# Master.net
KiCad netlist of a schematic drawn in Altium Designer
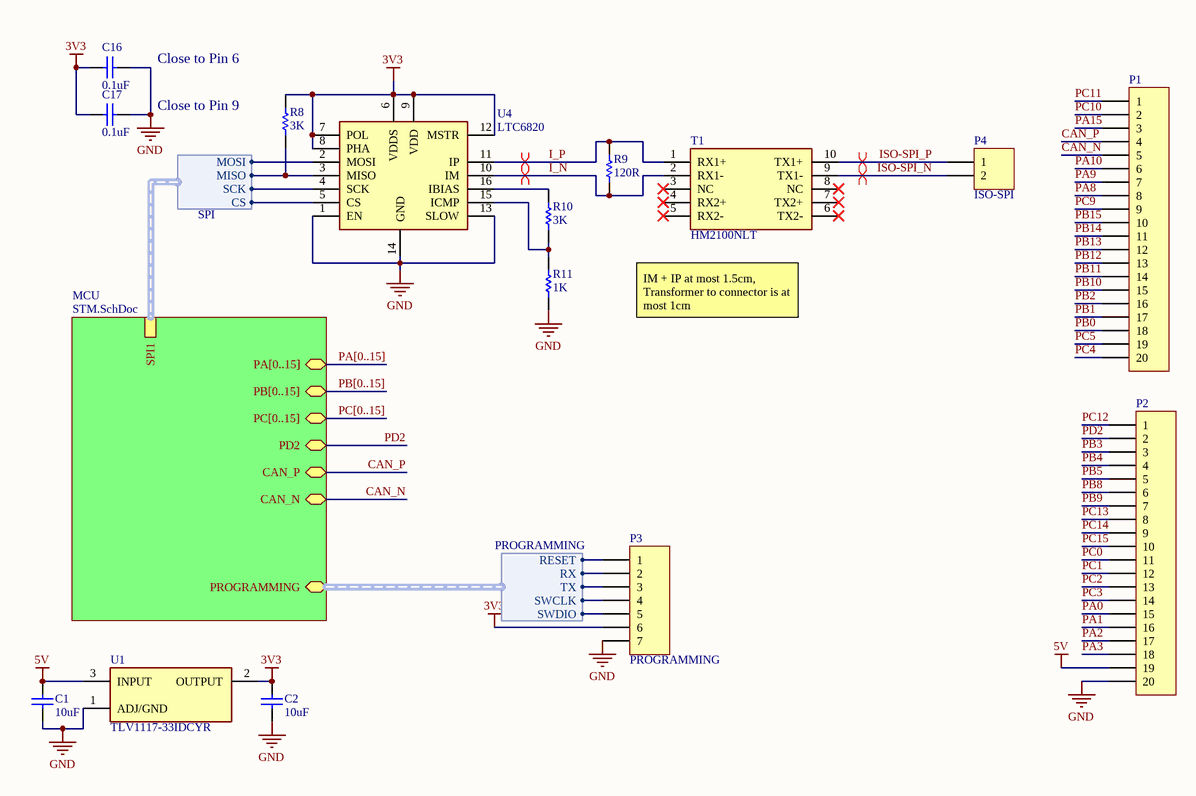
[diagram p0: Master.SchDoc]

(export (version "E")
  (design (tool "Eeschema 10.0.6"))
  (components
    (comp (ref "C1")
      (value "10uF")
      (footprint "0805 - Capacitor")
      (description "Nonpolarized Capacitor")
      (fields
        (field (name "MANUFACTURER") "Murata")
        (field (name "MANUFACTURER PART NUMBER") "GRM21BR71A106KA73K")
      )
      (libsource (lib "General") (part "Capacitor - Nonpolarized"))
    )
    (comp (ref "C2")
      (value "10uF")
      (footprint "0805 - Capacitor")
      (description "Nonpolarized Capacitor")
      (fields
        (field (name "MANUFACTURER") "Murata")
        (field (name "MANUFACTURER PART NUMBER") "GRM21BR71A106KA73K")
      )
      (libsource (lib "General") (part "Capacitor - Nonpolarized"))
    )
    (comp (ref "C16")
      (value "0.1uF")
      (footprint "0805 - Capacitor")
      (description "Nonpolarized Capacitor")
      (fields
        (field (name "MANUFACTURER") "Yageo")
        (field (name "MANUFACTURER PART NUMBER") "CC0805KRX7R9BB104")
      )
      (libsource (lib "General") (part "Capacitor - Nonpolarized"))
    )
    (comp (ref "C17")
      (value "0.1uF")
      (footprint "0805 - Capacitor")
      (description "Nonpolarized Capacitor")
      (fields
        (field (name "MANUFACTURER") "Yageo")
        (field (name "MANUFACTURER PART NUMBER") "CC0805KRX7R9BB104")
      )
      (libsource (lib "General") (part "Capacitor - Nonpolarized"))
    )
    (comp (ref "P1")
      (value "1x20 Header")
      (footprint "HDR1X20")
      (description "1x20 Pin Header")
      (libsource (lib "GeneralConnectors") (part "1x20 Header"))
    )
    (comp (ref "P2")
      (value "1x20 Header")
      (footprint "HDR1X20")
      (description "1x20 Pin Header")
      (libsource (lib "GeneralConnectors") (part "1x20 Header"))
    )
    (comp (ref "P3")
      (value "PROGRAMMING")
      (footprint "HDR1X7")
      (description "1x7 Pin Header")
      (libsource (lib "GeneralConnectors") (part "1x7 Header"))
    )
    (comp (ref "P4")
      (value "ISO-SPI")
      (footprint "HDR1X2")
      (description "1x2 Pin Header")
      (libsource (lib "GeneralConnectors") (part "1x2 Header"))
    )
    (comp (ref "R8")
      (value "3K")
      (footprint "0603 - Resistor")
      (description "Resistor")
      (fields
        (field (name "MANUFACTURER PART NUMBER") "RC0603FR-073KL")
        (field (name "MANUFACTURER") "Yageo")
      )
      (libsource (lib "General") (part "Resistor"))
    )
    (comp (ref "R9")
      (value "120R")
      (footprint "0603 - Resistor")
      (description "Resistor")
      (fields
        (field (name "MANUFACTURER PART NUMBER") "RC0603FR-07120RL")
        (field (name "MANUFACTURER") "Yageo")
      )
      (libsource (lib "General") (part "Resistor"))
    )
    (comp (ref "R10")
      (value "3K")
      (footprint "0603 - Resistor")
      (description "Resistor")
      (fields
        (field (name "MANUFACTURER PART NUMBER") "RC0603FR-073KL")
        (field (name "MANUFACTURER") "Yageo")
      )
      (libsource (lib "General") (part "Resistor"))
    )
    (comp (ref "R11")
      (value "1K")
      (footprint "0603 - Resistor")
      (description "Resistor")
      (fields
        (field (name "MANUFACTURER PART NUMBER") "RC0603FR-071KL")
        (field (name "MANUFACTURER") "Yageo")
      )
      (libsource (lib "General") (part "Resistor"))
    )
    (comp (ref "T1")
      (value "HM2100NLT")
      (footprint "HM2100NLT")
      (description "Pulse Transformer 1:1 Surface Mount 150µH, 450µH")
      (fields (field (name "MANUFACTURER") "Pulse Electronics"))
      (libsource (lib "GeneralComponents") (part "HM2100NLT"))
    )
    (comp (ref "U1")
      (value "TLV1117-33IDCYR")
      (footprint "TLV1117")
      (description "Linear Voltage Regulator IC 3.3V 800MA SOT223-4")
      (fields (field (name "MANUFACTURER") "Texas Instruments"))
      (libsource (lib "GeneralComponents") (part "TLV1117-33IDCYR"))
    )
    (comp (ref "U4")
      (value "LTC6820")
      (footprint "LTC6820")
      (fields
        (field (name "MANUFACTURER") "Analog Devices")
        (field (name "MANUFACTURER PART NUMBER") "LTC6820IMS#TRPBF")
      )
      (libsource (lib "BMS") (part "LTC6820"))
    )
  )
  (nets
    (net (code "16") (name "/CAN_N") (class "Default")
      (node (ref "P1") (pin "5") (pinfunction "5_5") (pintype "passive"))
    )
    (net (code "17") (name "/CAN_P") (class "Default")
      (node (ref "P1") (pin "4") (pinfunction "4_4") (pintype "passive"))
    )
    (net (code "18") (name "/CS") (class "Default")
      (node (ref "U4") (pin "5") (pinfunction "CS_5") (pintype "passive"))
    )
    (net (code "19") (name "/ISO-SPI_N") (class "Default")
      (node (ref "P4") (pin "2") (pinfunction "2_2") (pintype "passive"))
      (node (ref "T1") (pin "9") (pinfunction "TX1-_9") (pintype "passive"))
    )
    (net (code "20") (name "/ISO-SPI_P") (class "Default")
      (node (ref "P4") (pin "1") (pinfunction "1_1") (pintype "passive"))
      (node (ref "T1") (pin "10") (pinfunction "TX1+_10") (pintype "passive"))
    )
    (net (code "21") (name "/I_N") (class "Default")
      (node (ref "R9") (pin "1") (pinfunction "1_1") (pintype "passive"))
      (node (ref "T1") (pin "2") (pinfunction "RX1-_2") (pintype "passive"))
      (node (ref "U4") (pin "10") (pinfunction "IM_10") (pintype "passive"))
    )
    (net (code "22") (name "/I_P") (class "Default")
      (node (ref "R9") (pin "2") (pinfunction "2_2") (pintype "passive"))
      (node (ref "T1") (pin "1") (pinfunction "RX1+_1") (pintype "passive"))
      (node (ref "U4") (pin "11") (pinfunction "IP_11") (pintype "passive"))
    )
    (net (code "23") (name "/MISO") (class "Default")
      (node (ref "R8") (pin "1") (pinfunction "1_1") (pintype "passive"))
      (node (ref "U4") (pin "3") (pinfunction "MISO_3") (pintype "passive"))
    )
    (net (code "24") (name "/MOSI") (class "Default")
      (node (ref "U4") (pin "2") (pinfunction "MOSI_2") (pintype "passive"))
    )
    (net (code "25") (name "/PA0") (class "Default")
      (node (ref "P2") (pin "15") (pinfunction "15_15") (pintype "passive"))
    )
    (net (code "26") (name "/PA1") (class "Default")
      (node (ref "P2") (pin "16") (pinfunction "16_16") (pintype "passive"))
    )
    (net (code "27") (name "/PA2") (class "Default")
      (node (ref "P2") (pin "17") (pinfunction "17_17") (pintype "passive"))
    )
    (net (code "28") (name "/PA3") (class "Default")
      (node (ref "P2") (pin "18") (pinfunction "18_18") (pintype "passive"))
    )
    (net (code "29") (name "/PA8") (class "Default")
      (node (ref "P1") (pin "8") (pinfunction "8_8") (pintype "passive"))
    )
    (net (code "30") (name "/PA9") (class "Default")
      (node (ref "P1") (pin "7") (pinfunction "7_7") (pintype "passive"))
    )
    (net (code "31") (name "/PA10") (class "Default")
      (node (ref "P1") (pin "6") (pinfunction "6_6") (pintype "passive"))
    )
    (net (code "32") (name "/PA15") (class "Default")
      (node (ref "P1") (pin "3") (pinfunction "3_3") (pintype "passive"))
    )
    (net (code "34") (name "/PB0") (class "Default")
      (node (ref "P1") (pin "18") (pinfunction "18_18") (pintype "passive"))
    )
    (net (code "35") (name "/PB1") (class "Default")
      (node (ref "P1") (pin "17") (pinfunction "17_17") (pintype "passive"))
    )
    (net (code "36") (name "/PB2") (class "Default")
      (node (ref "P1") (pin "16") (pinfunction "16_16") (pintype "passive"))
    )
    (net (code "37") (name "/PB3") (class "Default")
      (node (ref "P2") (pin "3") (pinfunction "3_3") (pintype "passive"))
    )
    (net (code "38") (name "/PB4") (class "Default")
      (node (ref "P2") (pin "4") (pinfunction "4_4") (pintype "passive"))
    )
    (net (code "39") (name "/PB5") (class "Default")
      (node (ref "P2") (pin "5") (pinfunction "5_5") (pintype "passive"))
    )
    (net (code "40") (name "/PB8") (class "Default")
      (node (ref "P2") (pin "6") (pinfunction "6_6") (pintype "passive"))
    )
    (net (code "41") (name "/PB9") (class "Default")
      (node (ref "P2") (pin "7") (pinfunction "7_7") (pintype "passive"))
    )
    (net (code "42") (name "/PB10") (class "Default")
      (node (ref "P1") (pin "15") (pinfunction "15_15") (pintype "passive"))
    )
    (net (code "43") (name "/PB11") (class "Default")
      (node (ref "P1") (pin "14") (pinfunction "14_14") (pintype "passive"))
    )
    (net (code "44") (name "/PB12") (class "Default")
      (node (ref "P1") (pin "13") (pinfunction "13_13") (pintype "passive"))
    )
    (net (code "45") (name "/PB13") (class "Default")
      (node (ref "P1") (pin "12") (pinfunction "12_12") (pintype "passive"))
    )
    (net (code "46") (name "/PB14") (class "Default")
      (node (ref "P1") (pin "11") (pinfunction "11_11") (pintype "passive"))
    )
    (net (code "47") (name "/PB15") (class "Default")
      (node (ref "P1") (pin "10") (pinfunction "10_10") (pintype "passive"))
    )
    (net (code "49") (name "/PC0") (class "Default")
      (node (ref "P2") (pin "11") (pinfunction "11_11") (pintype "passive"))
    )
    (net (code "50") (name "/PC1") (class "Default")
      (node (ref "P2") (pin "12") (pinfunction "12_12") (pintype "passive"))
    )
    (net (code "51") (name "/PC2") (class "Default")
      (node (ref "P2") (pin "13") (pinfunction "13_13") (pintype "passive"))
    )
    (net (code "52") (name "/PC3") (class "Default")
      (node (ref "P2") (pin "14") (pinfunction "14_14") (pintype "passive"))
    )
    (net (code "53") (name "/PC4") (class "Default")
      (node (ref "P1") (pin "20") (pinfunction "20_20") (pintype "passive"))
    )
    (net (code "54") (name "/PC5") (class "Default")
      (node (ref "P1") (pin "19") (pinfunction "19_19") (pintype "passive"))
    )
    (net (code "55") (name "/PC9") (class "Default")
      (node (ref "P1") (pin "9") (pinfunction "9_9") (pintype "passive"))
    )
    (net (code "56") (name "/PC10") (class "Default")
      (node (ref "P1") (pin "2") (pinfunction "2_2") (pintype "passive"))
    )
    (net (code "57") (name "/PC11") (class "Default")
      (node (ref "P1") (pin "1") (pinfunction "1_1") (pintype "passive"))
    )
    (net (code "58") (name "/PC12") (class "Default")
      (node (ref "P2") (pin "1") (pinfunction "1_1") (pintype "passive"))
    )
    (net (code "59") (name "/PC13") (class "Default")
      (node (ref "P2") (pin "8") (pinfunction "8_8") (pintype "passive"))
    )
    (net (code "60") (name "/PC14") (class "Default")
      (node (ref "P2") (pin "9") (pinfunction "9_9") (pintype "passive"))
    )
    (net (code "61") (name "/PC15") (class "Default")
      (node (ref "P2") (pin "10") (pinfunction "10_10") (pintype "passive"))
    )
    (net (code "63") (name "/PD2") (class "Default")
      (node (ref "P2") (pin "2") (pinfunction "2_2") (pintype "passive"))
    )
    (net (code "64") (name "/RESET") (class "Default")
      (node (ref "P3") (pin "1") (pinfunction "1_1") (pintype "passive"))
    )
    (net (code "65") (name "/RX") (class "Default")
      (node (ref "P3") (pin "2") (pinfunction "2_2") (pintype "passive"))
    )
    (net (code "66") (name "/SCK") (class "Default")
      (node (ref "U4") (pin "4") (pinfunction "SCK_4") (pintype "passive"))
    )
    (net (code "67") (name "/SWCLK") (class "Default")
      (node (ref "P3") (pin "4") (pinfunction "4_4") (pintype "passive"))
    )
    (net (code "68") (name "/SWDIO") (class "Default")
      (node (ref "P3") (pin "5") (pinfunction "5_5") (pintype "passive"))
    )
    (net (code "69") (name "/TX") (class "Default")
      (node (ref "P3") (pin "3") (pinfunction "3_3") (pintype "passive"))
    )
    (net (code "72") (name "3V3") (class "Default")
      (node (ref "C16") (pin "2") (pinfunction "2_2") (pintype "passive"))
      (node (ref "C17") (pin "2") (pinfunction "2_2") (pintype "passive"))
      (node (ref "C2") (pin "2") (pinfunction "2_2") (pintype "passive"))
      (node (ref "P3") (pin "6") (pinfunction "6_6") (pintype "passive"))
      (node (ref "R8") (pin "2") (pinfunction "2_2") (pintype "passive"))
      (node (ref "U1") (pin "2") (pinfunction "OUTPUT_2") (pintype "passive"))
      (node (ref "U4") (pin "12") (pinfunction "MSTR_12") (pintype "passive"))
      (node (ref "U4") (pin "6") (pinfunction "VDDS_6") (pintype "passive"))
      (node (ref "U4") (pin "7") (pinfunction "POL_7") (pintype "passive"))
      (node (ref "U4") (pin "8") (pinfunction "PHA_8") (pintype "passive"))
      (node (ref "U4") (pin "9") (pinfunction "VDD_9") (pintype "passive"))
    )
    (net (code "73") (name "5V") (class "Default")
      (node (ref "C1") (pin "2") (pinfunction "2_2") (pintype "passive"))
      (node (ref "P2") (pin "19") (pinfunction "19_19") (pintype "passive"))
      (node (ref "U1") (pin "3") (pinfunction "INPUT_3") (pintype "passive"))
    )
    (net (code "74") (name "GND") (class "Default")
      (node (ref "C1") (pin "1") (pinfunction "1_1") (pintype "passive"))
      (node (ref "C16") (pin "1") (pinfunction "1_1") (pintype "passive"))
      (node (ref "C17") (pin "1") (pinfunction "1_1") (pintype "passive"))
      (node (ref "C2") (pin "1") (pinfunction "1_1") (pintype "passive"))
      (node (ref "P2") (pin "20") (pinfunction "20_20") (pintype "passive"))
      (node (ref "P3") (pin "7") (pinfunction "7_7") (pintype "passive"))
      (node (ref "R11") (pin "1") (pinfunction "1_1") (pintype "passive"))
      (node (ref "U1") (pin "1") (pinfunction "ADJ/GND_1") (pintype "passive"))
      (node (ref "U4") (pin "1") (pinfunction "EN_1") (pintype "passive"))
      (node (ref "U4") (pin "13") (pinfunction "SLOW_13") (pintype "passive"))
      (node (ref "U4") (pin "14") (pinfunction "GND_14") (pintype "passive"))
    )
    (net (code "75") (name "Net-(U4-IBIAS)") (class "Default")
      (node (ref "R10") (pin "2") (pinfunction "2_2") (pintype "passive"))
      (node (ref "U4") (pin "16") (pinfunction "IBIAS_16") (pintype "passive"))
    )
    (net (code "76") (name "Net-(U4-ICMP)") (class "Default")
      (node (ref "R10") (pin "1") (pinfunction "1_1") (pintype "passive"))
      (node (ref "R11") (pin "2") (pinfunction "2_2") (pintype "passive"))
      (node (ref "U4") (pin "15") (pinfunction "ICMP_15") (pintype "passive"))
    )
    (net (code "77") (name "unconnected-(T1-NC-Pad3)") (class "Default")
      (node (ref "T1") (pin "3") (pinfunction "NC_3") (pintype "passive+no_connect"))
    )
    (net (code "78") (name "unconnected-(T1-NC-Pad8)") (class "Default")
      (node (ref "T1") (pin "8") (pinfunction "NC_8") (pintype "passive+no_connect"))
    )
    (net (code "79") (name "unconnected-(T1-RX2+-Pad4)") (class "Default")
      (node (ref "T1") (pin "4") (pinfunction "RX2+_4") (pintype "passive+no_connect"))
    )
    (net (code "80") (name "unconnected-(T1-RX2--Pad5)") (class "Default")
      (node (ref "T1") (pin "5") (pinfunction "RX2-_5") (pintype "passive+no_connect"))
    )
    (net (code "81") (name "unconnected-(T1-TX2+-Pad7)") (class "Default")
      (node (ref "T1") (pin "7") (pinfunction "TX2+_7") (pintype "passive+no_connect"))
    )
    (net (code "82") (name "unconnected-(T1-TX2--Pad6)") (class "Default")
      (node (ref "T1") (pin "6") (pinfunction "TX2-_6") (pintype "passive+no_connect"))
    )
  )
)
